# pidbot.net
KiCad netlist of a schematic drawn in Altium Designer
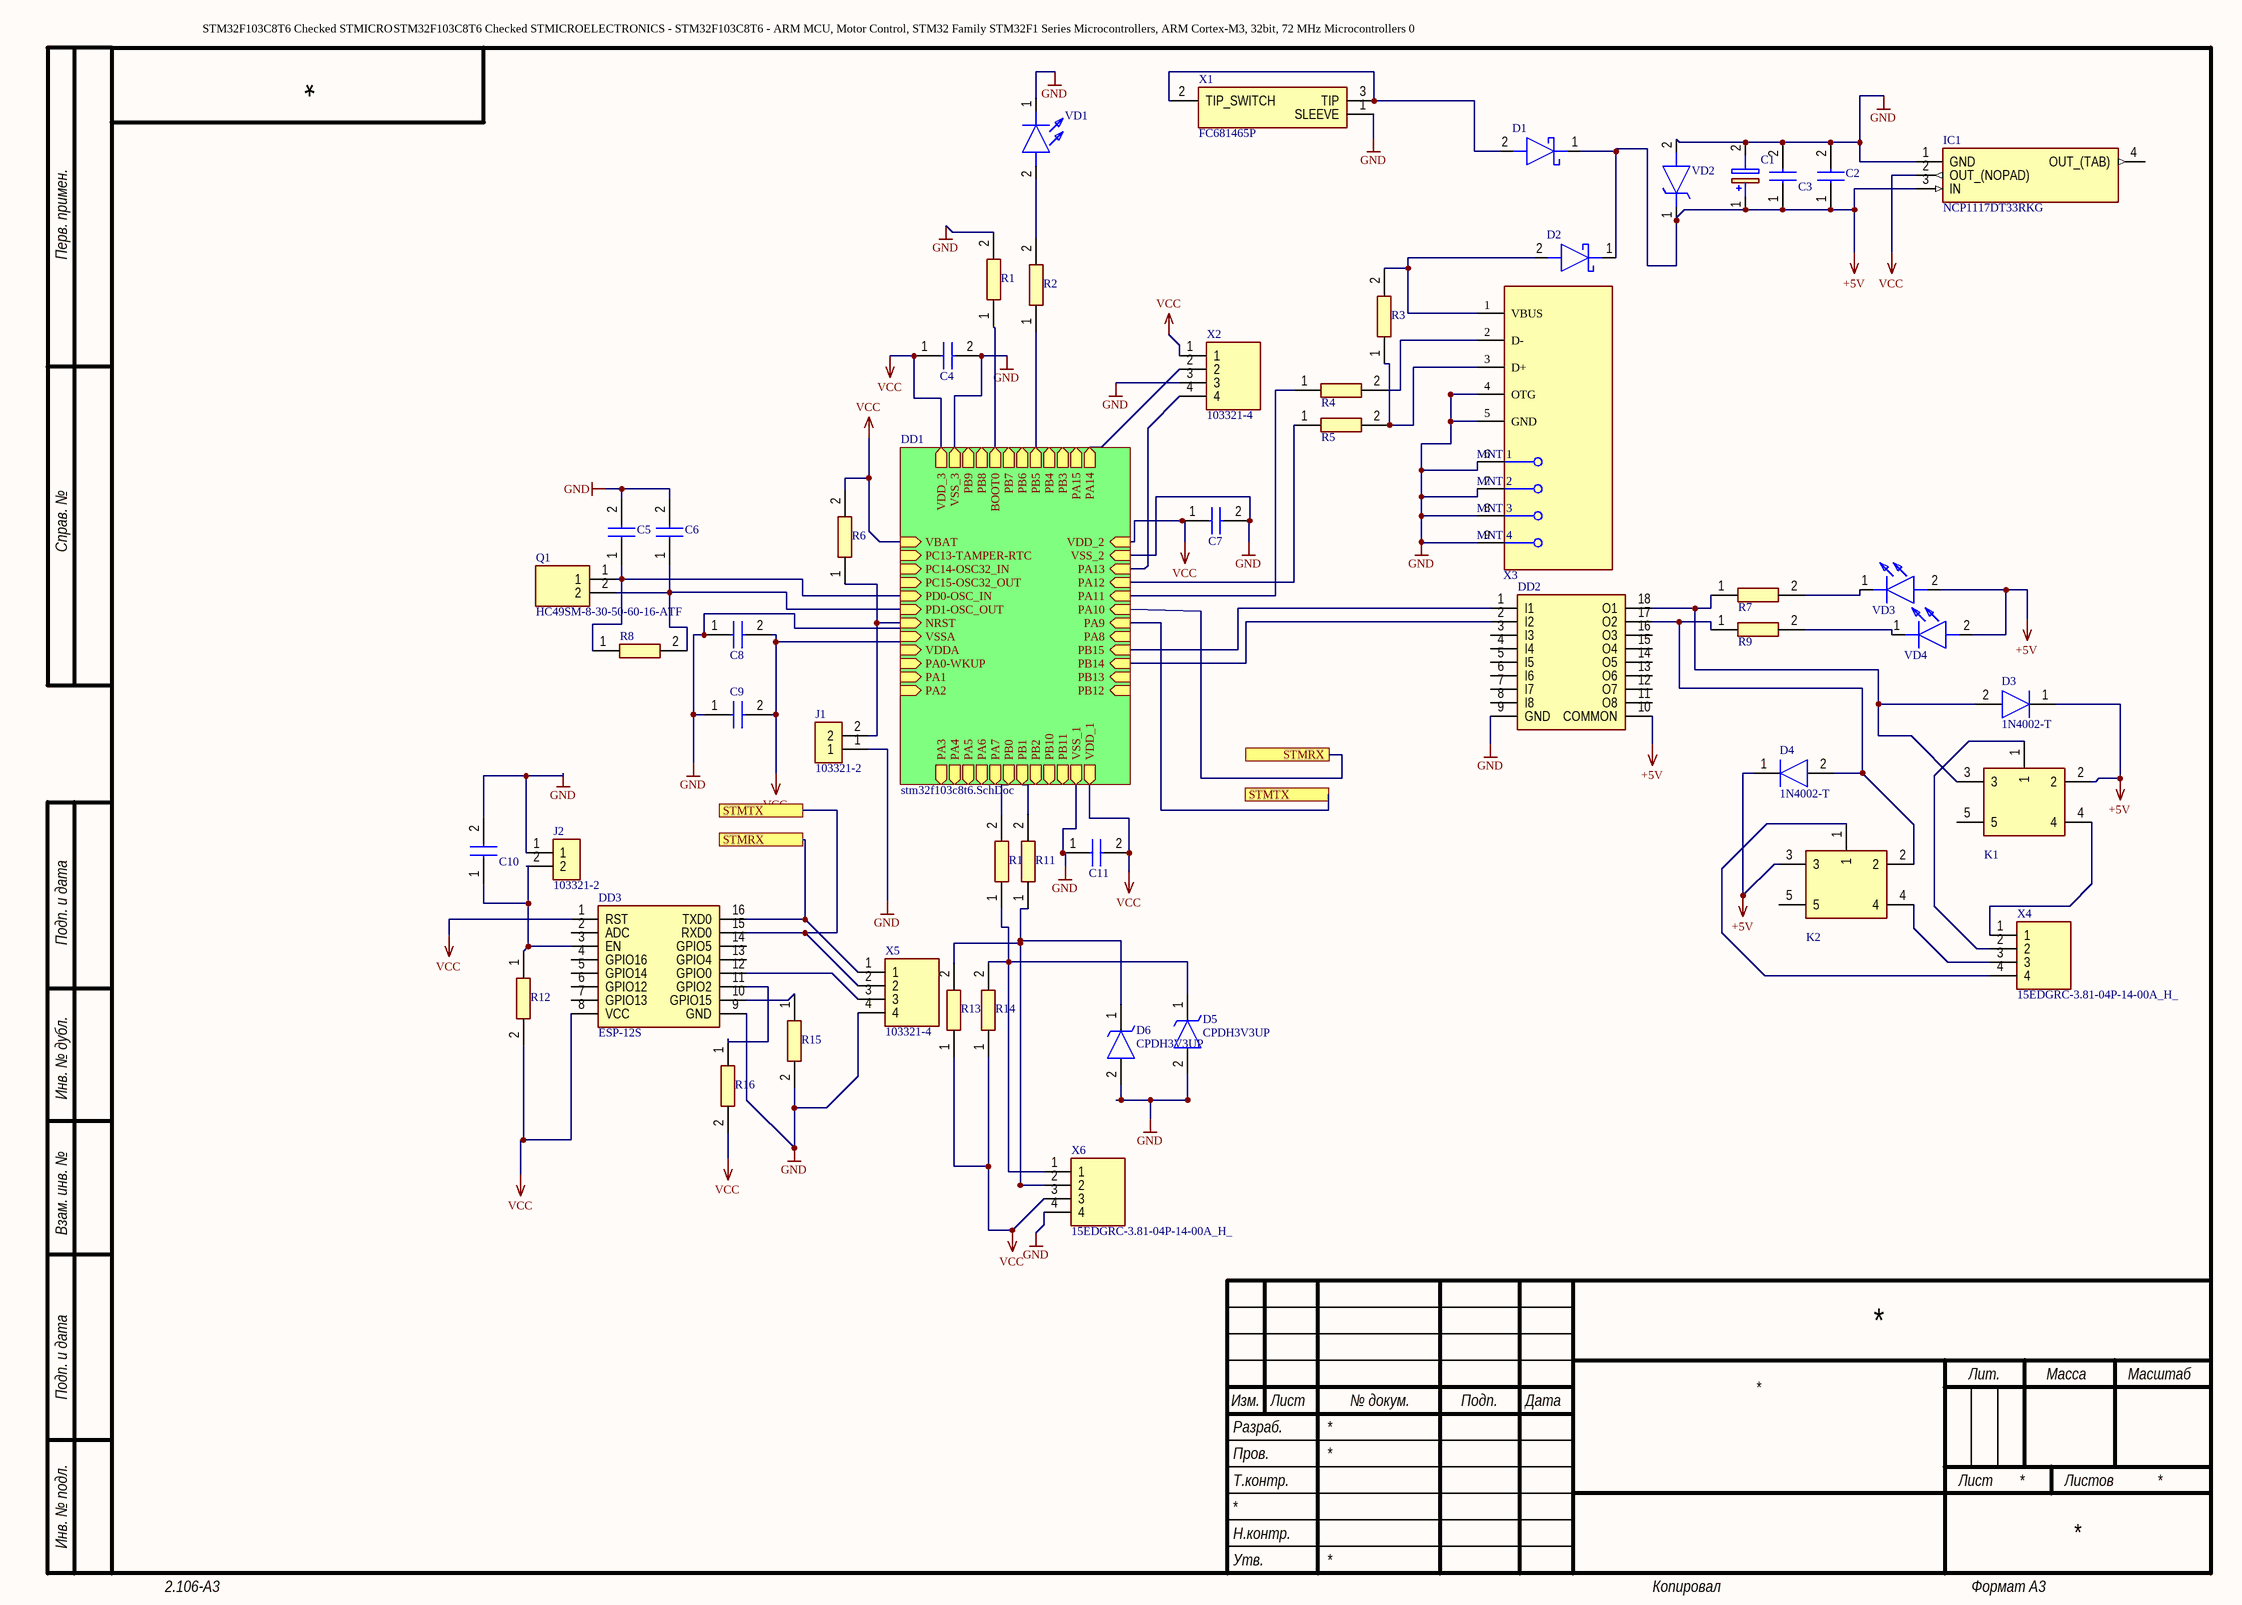
[diagram p0: pidbot.SchDoc]

(export (version "E")
  (design (tool "Eeschema 10.0.6"))
  (components
    (comp (ref "C1")
      (value "470uF(CPOL)")
      (footprint "SamacSys:CAPAE530X610N")
      (description "Capacitor Polarised")
      (fields (field (name "MANUFACTURER_PART_NUMBER") "EEEFK0J470R"))
      (libsource (lib "*") (part "EEEFK0J470R"))
    )
    (comp (ref "C2")
      (value "10uF(0805)")
      (footprint "SamacSys:CAPC2012X145N")
      (description "Capacitor")
      (fields
        (field (name "MANUFACTURER_PART_NUMBER") "C2012X6S1A106K125AB")
        (field (name "MOUSER PART NUMBER") "810-C2012X6S1A106K1B")
      )
      (libsource (lib "*") (part "C2012X6S1A106K125AB"))
    )
    (comp (ref "C3")
      (value "0.1uF(0603)")
      (footprint "SamacSys:CAPC1608X90N")
      (description "Capacitor")
      (fields
        (field (name "MANUFACTURER_PART_NUMBER") "06035A270FAT2A")
        (field (name "MOUSER PART NUMBER") "581-06035A270FAT2A")
      )
      (libsource (lib "*") (part "06035A270FAT2A"))
    )
    (comp (ref "C4")
      (value "0.1uF(0603)")
      (footprint "SamacSys:CAPC1608X90N")
      (description "Capacitor")
      (fields
        (field (name "MANUFACTURER_PART_NUMBER") "06035A270FAT2A")
        (field (name "MOUSER PART NUMBER") "581-06035A270FAT2A")
      )
      (libsource (lib "*") (part "06035A270FAT2A"))
    )
    (comp (ref "C5")
      (value "27pF(0603)")
      (footprint "SamacSys:CAPC1608X90N")
      (description "Capacitor")
      (fields
        (field (name "MANUFACTURER_PART_NUMBER") "06035A270FAT2A")
        (field (name "MOUSER PART NUMBER") "581-06035A270FAT2A")
      )
      (libsource (lib "*") (part "06035A270FAT2A"))
    )
    (comp (ref "C6")
      (value "27pF(0603)")
      (footprint "SamacSys:CAPC1608X90N")
      (description "Capacitor")
      (fields
        (field (name "MANUFACTURER_PART_NUMBER") "06035A270FAT2A")
        (field (name "MOUSER PART NUMBER") "581-06035A270FAT2A")
      )
      (libsource (lib "*") (part "06035A270FAT2A"))
    )
    (comp (ref "C7")
      (value "0.1uF(0603)")
      (footprint "SamacSys:CAPC1608X90N")
      (description "Capacitor")
      (fields
        (field (name "MANUFACTURER_PART_NUMBER") "06035A270FAT2A")
        (field (name "MOUSER PART NUMBER") "581-06035A270FAT2A")
      )
      (libsource (lib "*") (part "06035A270FAT2A"))
    )
    (comp (ref "C8")
      (value "0.1uF(0603)")
      (footprint "SamacSys:CAPC1608X90N")
      (description "Capacitor")
      (fields
        (field (name "MANUFACTURER_PART_NUMBER") "06035A270FAT2A")
        (field (name "MOUSER PART NUMBER") "581-06035A270FAT2A")
      )
      (libsource (lib "*") (part "06035A270FAT2A"))
    )
    (comp (ref "C9")
      (value "10uF(0805)")
      (footprint "SamacSys:CAPC2012X145N")
      (description "Capacitor")
      (fields
        (field (name "MANUFACTURER_PART_NUMBER") "C2012X6S1A106K125AB")
        (field (name "MOUSER PART NUMBER") "810-C2012X6S1A106K1B")
      )
      (libsource (lib "*") (part "C2012X6S1A106K125AB"))
    )
    (comp (ref "C10")
      (value "10uF(0805)")
      (footprint "SamacSys:CAPC2012X145N")
      (description "Capacitor")
      (fields
        (field (name "MANUFACTURER_PART_NUMBER") "C2012X6S1A106K125AB")
        (field (name "MOUSER PART NUMBER") "810-C2012X6S1A106K1B")
      )
      (libsource (lib "*") (part "C2012X6S1A106K125AB"))
    )
    (comp (ref "C11")
      (value "0.1uF(0603)")
      (footprint "SamacSys:CAPC1608X90N")
      (description "Capacitor")
      (fields
        (field (name "MANUFACTURER_PART_NUMBER") "06035A270FAT2A")
        (field (name "MOUSER PART NUMBER") "581-06035A270FAT2A")
      )
      (libsource (lib "*") (part "06035A270FAT2A"))
    )
    (comp (ref "D1")
      (value "SS14FL")
      (footprint "SamacSys:SODFL3617X108N")
      (description "Schottky Diode")
      (fields (field (name "MOUSER PART NUMBER") "512-SS14FL"))
      (libsource (lib "*") (part "SS14FL"))
    )
    (comp (ref "D2")
      (value "SS14FL")
      (footprint "SamacSys:SODFL3617X108N")
      (description "Schottky Diode")
      (fields (field (name "MOUSER PART NUMBER") "512-SS14FL"))
      (libsource (lib "*") (part "SS14FL"))
    )
    (comp (ref "D3")
      (value "1N4002-T")
      (footprint "SamacSys:DIOAD1408W86L464D236")
      (description "Diode")
      (fields (field (name "MOUSER PART NUMBER") "621-1N4002-T"))
      (libsource (lib "*") (part "1N4002-T"))
    )
    (comp (ref "D4")
      (value "1N4002-T")
      (footprint "SamacSys:DIOAD1408W86L464D236")
      (description "Diode")
      (fields (field (name "MOUSER PART NUMBER") "621-1N4002-T"))
      (libsource (lib "*") (part "1N4002-T"))
    )
    (comp (ref "D5")
      (value "CPDH3V3UP")
      (footprint "SamacSys:CPDH3V3UP")
      (description "TVS Diode (Uni-directional)")
      (fields (field (name "MOUSER PART NUMBER") "750-CPDH3V3UP"))
      (libsource (lib "*") (part "CPDH3V3UP"))
    )
    (comp (ref "D6")
      (value "CPDH3V3UP")
      (footprint "SamacSys:CPDH3V3UP")
      (description "TVS Diode (Uni-directional)")
      (fields (field (name "MOUSER PART NUMBER") "750-CPDH3V3UP"))
      (libsource (lib "*") (part "CPDH3V3UP"))
    )
    (comp (ref "DD2")
      (value "ULN2803AFWG,C,EL")
      (footprint "SamacSys:SOIC127P1032X285-18N")
      (description "Integrated Circuit")
      (libsource (lib "*") (part "ULN2803AFWG,C,EL"))
    )
    (comp (ref "DD3")
      (value "ESP-12S")
      (footprint "SamacSys:ESP12S")
      (description "Integrated Circuit")
      (fields (field (name "MOUSER PART NUMBER") "223-ESP-12S"))
      (libsource (lib "*") (part "ESP-12S"))
    )
    (comp (ref "IC1")
      (value "NCP1117DT33RKG")
      (footprint "SamacSys:TO229P990X238-4N")
      (description "Integrated Circuit")
      (fields (field (name "MOUSER PART NUMBER") "863-NCP1117DT33RKG"))
      (libsource (lib "*") (part "NCP1117DT33RKG"))
    )
    (comp (ref "J1")
      (value "103321-2")
      (footprint "SamacSys:HDRV4W66P0X254_1X2_975X234X1036P")
      (description "Connector")
      (fields
        (field (name "MANUFACTURER_PART_NUMBER") "103321-4")
        (field (name "MOUSER PART NUMBER") "571-1033214")
      )
      (libsource (lib "") (part "103321-2_1"))
    )
    (comp (ref "J2")
      (value "103321-2")
      (footprint "SamacSys:HDRV4W66P0X254_1X2_975X234X1036P")
      (description "Connector")
      (fields
        (field (name "MANUFACTURER_PART_NUMBER") "103321-4")
        (field (name "MOUSER PART NUMBER") "571-1033214")
      )
      (libsource (lib "SamacSys") (part "103321-2"))
    )
    (comp (ref "K1")
      (value "SRD-05VDC-SL-C")
      (footprint "SamacSys:SRD")
      (description "Relay or Contactor")
      (libsource (lib "*") (part "SRD-05VDC-SL-C"))
    )
    (comp (ref "K2")
      (value "SRD-05VDC-SL-C")
      (footprint "SamacSys:SRD")
      (description "Relay or Contactor")
      (libsource (lib "*") (part "SRD-05VDC-SL-C"))
    )
    (comp (ref "Q1")
      (value "HC49SM-8-30-50-60-16-ATF")
      (footprint "SamacSys:HC49SM830506016ATF")
      (description "Crystal or Oscillator")
      (libsource (lib "*") (part "HC49SM-8-30-50-60-16-ATF"))
    )
    (comp (ref "R1")
      (value "10K(0603)")
      (footprint "SamacSys:RESC1608X50N")
      (description "Resistor")
      (fields
        (field (name "MANUFACTURER_PART_NUMBER") "CRCW06031M10FKEA")
        (field (name "MOUSER PART NUMBER") "71-CRCW06031M10FKEA")
      )
      (libsource (lib "") (part "CRCW06031M10FKEA_2"))
    )
    (comp (ref "R2")
      (value "330(0603)")
      (footprint "SamacSys:RESC1608X50N")
      (description "Resistor")
      (fields
        (field (name "MANUFACTURER_PART_NUMBER") "CRCW06031M10FKEA")
        (field (name "MOUSER PART NUMBER") "71-CRCW06031M10FKEA")
      )
      (libsource (lib "") (part "CRCW06031M10FKEA_2"))
    )
    (comp (ref "R3")
      (value "1500(0603)")
      (footprint "SamacSys:RESC1608X50N")
      (description "Resistor")
      (fields
        (field (name "MANUFACTURER_PART_NUMBER") "CRCW06031M10FKEA")
        (field (name "MOUSER PART NUMBER") "71-CRCW06031M10FKEA")
      )
      (libsource (lib "") (part "CRCW06031M10FKEA_2"))
    )
    (comp (ref "R4")
      (value "22(0603)")
      (footprint "SamacSys:RESC1608X50N")
      (description "Resistor")
      (fields
        (field (name "MANUFACTURER_PART_NUMBER") "CRCW06031M10FKEA")
        (field (name "MOUSER PART NUMBER") "71-CRCW06031M10FKEA")
      )
      (libsource (lib "*") (part "CRCW06031M10FKEA"))
    )
    (comp (ref "R5")
      (value "22(0603)")
      (footprint "SamacSys:RESC1608X50N")
      (description "Resistor")
      (fields
        (field (name "MANUFACTURER_PART_NUMBER") "CRCW06031M10FKEA")
        (field (name "MOUSER PART NUMBER") "71-CRCW06031M10FKEA")
      )
      (libsource (lib "*") (part "CRCW06031M10FKEA"))
    )
    (comp (ref "R6")
      (value "10K(0603)")
      (footprint "SamacSys:RESC1608X50N")
      (description "Resistor")
      (fields
        (field (name "MANUFACTURER_PART_NUMBER") "CRCW06031M10FKEA")
        (field (name "MOUSER PART NUMBER") "71-CRCW06031M10FKEA")
      )
      (libsource (lib "") (part "CRCW06031M10FKEA_2"))
    )
    (comp (ref "R7")
      (value "470(0603)")
      (footprint "SamacSys:RESC1608X50N")
      (description "Resistor")
      (fields
        (field (name "MANUFACTURER_PART_NUMBER") "CRCW06031M10FKEA")
        (field (name "MOUSER PART NUMBER") "71-CRCW06031M10FKEA")
      )
      (libsource (lib "*") (part "CRCW06031M10FKEA"))
    )
    (comp (ref "R8")
      (value "1M(0603)")
      (footprint "SamacSys:RESC1608X50N")
      (description "Resistor")
      (fields
        (field (name "MANUFACTURER_PART_NUMBER") "CRCW06031M10FKEA")
        (field (name "MOUSER PART NUMBER") "71-CRCW06031M10FKEA")
      )
      (libsource (lib "*") (part "CRCW06031M10FKEA"))
    )
    (comp (ref "R9")
      (value "470(0603)")
      (footprint "SamacSys:RESC1608X50N")
      (description "Resistor")
      (fields
        (field (name "MANUFACTURER_PART_NUMBER") "CRCW06031M10FKEA")
        (field (name "MOUSER PART NUMBER") "71-CRCW06031M10FKEA")
      )
      (libsource (lib "*") (part "CRCW06031M10FKEA"))
    )
    (comp (ref "R10")
      (value "10(0603)")
      (footprint "SamacSys:RESC1608X50N")
      (description "Resistor")
      (fields
        (field (name "MANUFACTURER_PART_NUMBER") "CRCW06031M10FKEA")
        (field (name "MOUSER PART NUMBER") "71-CRCW06031M10FKEA")
      )
      (libsource (lib "") (part "CRCW06031M10FKEA_2"))
    )
    (comp (ref "R11")
      (value "10(0603)")
      (footprint "SamacSys:RESC1608X50N")
      (description "Resistor")
      (fields
        (field (name "MANUFACTURER_PART_NUMBER") "CRCW06031M10FKEA")
        (field (name "MOUSER PART NUMBER") "71-CRCW06031M10FKEA")
      )
      (libsource (lib "") (part "CRCW06031M10FKEA_2"))
    )
    (comp (ref "R12")
      (value "1K(0603)")
      (footprint "SamacSys:RESC1608X50N")
      (description "Resistor")
      (fields
        (field (name "MANUFACTURER_PART_NUMBER") "CRCW06031M10FKEA")
        (field (name "MOUSER PART NUMBER") "71-CRCW06031M10FKEA")
      )
      (libsource (lib "") (part "CRCW06031M10FKEA_1"))
    )
    (comp (ref "R13")
      (value "10K(0603)")
      (footprint "SamacSys:RESC1608X50N")
      (description "Resistor")
      (fields
        (field (name "MANUFACTURER_PART_NUMBER") "CRCW06031M10FKEA")
        (field (name "MOUSER PART NUMBER") "71-CRCW06031M10FKEA")
      )
      (libsource (lib "") (part "CRCW06031M10FKEA_2"))
    )
    (comp (ref "R14")
      (value "10K(0603)")
      (footprint "SamacSys:RESC1608X50N")
      (description "Resistor")
      (fields
        (field (name "MANUFACTURER_PART_NUMBER") "CRCW06031M10FKEA")
        (field (name "MOUSER PART NUMBER") "71-CRCW06031M10FKEA")
      )
      (libsource (lib "") (part "CRCW06031M10FKEA_2"))
    )
    (comp (ref "R15")
      (value "1K(0603)")
      (footprint "SamacSys:RESC1608X50N")
      (description "Resistor")
      (fields
        (field (name "MANUFACTURER_PART_NUMBER") "CRCW06031M10FKEA")
        (field (name "MOUSER PART NUMBER") "71-CRCW06031M10FKEA")
      )
      (libsource (lib "") (part "CRCW06031M10FKEA_1"))
    )
    (comp (ref "R16")
      (value "1K(0603)")
      (footprint "SamacSys:RESC1608X50N")
      (description "Resistor")
      (fields
        (field (name "MANUFACTURER_PART_NUMBER") "CRCW06031M10FKEA")
        (field (name "MOUSER PART NUMBER") "71-CRCW06031M10FKEA")
      )
      (libsource (lib "") (part "CRCW06031M10FKEA_1"))
    )
    (comp (ref "VD1")
      (value "KP-2012SGC")
      (footprint "SamacSys:LEDC2012X110N")
      (description "LED")
      (libsource (lib "*") (part "KP-2012SGC"))
    )
    (comp (ref "VD2")
      (value "1N4733AUR")
      (footprint "SamacSys:DO-213AB")
      (description "Zener Diode")
      (fields (field (name "MOUSER PART NUMBER") "494-1N4733AUR"))
      (libsource (lib "*") (part "1N4733AUR"))
    )
    (comp (ref "VD3")
      (value "KP-2012SGC")
      (footprint "SamacSys:LEDC2012X110N")
      (description "LED")
      (libsource (lib "*") (part "KP-2012SGC"))
    )
    (comp (ref "VD4")
      (value "KP-2012SGC")
      (footprint "SamacSys:LEDC2012X110N")
      (description "LED")
      (libsource (lib "*") (part "KP-2012SGC"))
    )
    (comp (ref "X1")
      (value "FC681465P")
      (footprint "SamacSys:FC681465P")
      (description "Connector")
      (libsource (lib "*") (part "FC681465P"))
    )
    (comp (ref "X2")
      (value "103321-4")
      (footprint "SamacSys:HDRV4W66P0X254_1X4_975X234X1036P")
      (description "Connector")
      (fields (field (name "MOUSER PART NUMBER") "571-1033214"))
      (libsource (lib "*") (part "103321-4"))
    )
    (comp (ref "X3") (value "*") (footprint "pidbot:Wurth_0_MFG") (libsource (lib "*") (part "629105150521")))
    (comp (ref "X4")
      (value "15EDGRC-3.81-04P-14-00A_H_")
      (footprint "SamacSys:SHDRRA4W80P0X381_1X4_1603X920X754P")
      (description "Connector")
      (fields (field (name "MANUFACTURER_PART_NUMBER") "15EDGRC-3.81-04P-14-00A(H)"))
      (libsource (lib "*") (part "15EDGRC-3.81-04P-14-00A_H_"))
    )
    (comp (ref "X5")
      (value "103321-4")
      (footprint "SamacSys:HDRV4W66P0X254_1X4_975X234X1036P")
      (description "Connector")
      (fields (field (name "MOUSER PART NUMBER") "571-1033214"))
      (libsource (lib "*") (part "103321-4"))
    )
    (comp (ref "X6")
      (value "15EDGRC-3.81-04P-14-00A_H_")
      (footprint "SamacSys:SHDRRA4W80P0X381_1X4_1603X920X754P")
      (description "Connector")
      (fields (field (name "MANUFACTURER_PART_NUMBER") "15EDGRC-3.81-04P-14-00A(H)"))
      (libsource (lib "*") (part "15EDGRC-3.81-04P-14-00A_H_"))
    )
  )
  (nets
    (net (code "1") (name "+5V") (class "Default")
      (node (ref "C1") (pin "1") (pinfunction "+_1") (pintype "passive"))
      (node (ref "C2") (pin "1") (pinfunction "1_1") (pintype "passive"))
      (node (ref "C3") (pin "1") (pinfunction "1_1") (pintype "passive"))
      (node (ref "D1") (pin "1") (pinfunction "K_1") (pintype "passive"))
      (node (ref "D2") (pin "1") (pinfunction "K_1") (pintype "passive"))
      (node (ref "D3") (pin "1") (pinfunction "K_1") (pintype "passive"))
      (node (ref "D4") (pin "1") (pinfunction "K_1") (pintype "passive"))
      (node (ref "DD2") (pin "10") (pinfunction "COMMON_10") (pintype "passive"))
      (node (ref "IC1") (pin "3") (pinfunction "IN_3") (pintype "input"))
      (node (ref "K1") (pin "2") (pinfunction "2_2") (pintype "passive"))
      (node (ref "K2") (pin "3") (pinfunction "3_3") (pintype "passive"))
      (node (ref "VD2") (pin "1") (pinfunction "K_1") (pintype "passive"))
      (node (ref "VD3") (pin "2") (pinfunction "A_2") (pintype "passive"))
      (node (ref "VD4") (pin "2") (pinfunction "A_2") (pintype "passive"))
    )
    (net (code "2") (name "/BOOT0") (class "Default")
      (node (ref "R1") (pin "1") (pinfunction "1_1") (pintype "passive"))
    )
    (net (code "3") (name "/NRST") (class "Default")
      (node (ref "J1") (pin "2") (pinfunction "2_2") (pintype "passive"))
      (node (ref "R6") (pin "1") (pinfunction "1_1") (pintype "passive"))
    )
    (net (code "13") (name "/PA11") (class "Default")
      (node (ref "R4") (pin "1") (pinfunction "1_1") (pintype "passive"))
    )
    (net (code "14") (name "/PA12") (class "Default")
      (node (ref "R5") (pin "1") (pinfunction "1_1") (pintype "passive"))
    )
    (net (code "15") (name "/PA13") (class "Default")
      (node (ref "X2") (pin "4") (pinfunction "4_4") (pintype "passive"))
    )
    (net (code "16") (name "/PA14") (class "Default")
      (node (ref "X2") (pin "2") (pinfunction "2_2") (pintype "passive"))
    )
    (net (code "18") (name "/PB0") (class "Default")
      (node (ref "R10") (pin "2") (pinfunction "2_2") (pintype "passive"))
    )
    (net (code "19") (name "/PB1") (class "Default")
      (node (ref "R11") (pin "2") (pinfunction "2_2") (pintype "passive"))
    )
    (net (code "23") (name "/PB5") (class "Default")
      (node (ref "R2") (pin "1") (pinfunction "1_1") (pintype "passive"))
    )
    (net (code "32") (name "/PB14") (class "Default")
      (node (ref "DD2") (pin "2") (pinfunction "I2_2") (pintype "passive"))
    )
    (net (code "33") (name "/PB15") (class "Default")
      (node (ref "DD2") (pin "1") (pinfunction "I1_1") (pintype "passive"))
    )
    (net (code "37") (name "/PD0-OSC_IN") (class "Default")
      (node (ref "C5") (pin "1") (pinfunction "1_1") (pintype "passive"))
      (node (ref "Q1") (pin "1") (pinfunction "1_1") (pintype "passive"))
      (node (ref "R8") (pin "1") (pinfunction "1_1") (pintype "passive"))
    )
    (net (code "38") (name "/PD1-OSC_OUT") (class "Default")
      (node (ref "C6") (pin "1") (pinfunction "1_1") (pintype "passive"))
      (node (ref "Q1") (pin "2") (pinfunction "2_2") (pintype "passive"))
      (node (ref "R8") (pin "2") (pinfunction "2_2") (pintype "passive"))
    )
    (net (code "39") (name "/STMRX") (class "Default")
      (node (ref "DD3") (pin "16") (pinfunction "TXD0_16") (pintype "passive"))
      (node (ref "X5") (pin "1") (pinfunction "1_1") (pintype "passive"))
    )
    (net (code "40") (name "/STMTX") (class "Default")
      (node (ref "DD3") (pin "15") (pinfunction "RXD0_15") (pintype "passive"))
      (node (ref "X5") (pin "2") (pinfunction "2_2") (pintype "passive"))
    )
    (net (code "41") (name "GND") (class "Default")
      (node (ref "C1") (pin "2") (pinfunction "-_2") (pintype "passive"))
      (node (ref "C10") (pin "2") (pinfunction "2_2") (pintype "passive"))
      (node (ref "C11") (pin "1") (pinfunction "1_1") (pintype "passive"))
      (node (ref "C2") (pin "2") (pinfunction "2_2") (pintype "passive"))
      (node (ref "C3") (pin "2") (pinfunction "2_2") (pintype "passive"))
      (node (ref "C4") (pin "2") (pinfunction "2_2") (pintype "passive"))
      (node (ref "C5") (pin "2") (pinfunction "2_2") (pintype "passive"))
      (node (ref "C6") (pin "2") (pinfunction "2_2") (pintype "passive"))
      (node (ref "C7") (pin "2") (pinfunction "2_2") (pintype "passive"))
      (node (ref "C8") (pin "1") (pinfunction "1_1") (pintype "passive"))
      (node (ref "C9") (pin "1") (pinfunction "1_1") (pintype "passive"))
      (node (ref "D5") (pin "2") (pinfunction "A_2") (pintype "passive"))
      (node (ref "D6") (pin "2") (pinfunction "A_2") (pintype "passive"))
      (node (ref "DD2") (pin "9") (pinfunction "GND_9") (pintype "passive"))
      (node (ref "DD3") (pin "9") (pinfunction "GND_9") (pintype "passive"))
      (node (ref "IC1") (pin "1") (pinfunction "GND_1") (pintype "power_in"))
      (node (ref "J1") (pin "1") (pinfunction "1_1") (pintype "passive"))
      (node (ref "J2") (pin "1") (pinfunction "1_1") (pintype "passive"))
      (node (ref "R1") (pin "2") (pinfunction "2_2") (pintype "passive"))
      (node (ref "R15") (pin "2") (pinfunction "2_2") (pintype "passive"))
      (node (ref "VD1") (pin "1") (pinfunction "K_1") (pintype "passive"))
      (node (ref "VD2") (pin "2") (pinfunction "A_2") (pintype "passive"))
      (node (ref "X1") (pin "1") (pinfunction "SLEEVE_1") (pintype "passive"))
      (node (ref "X2") (pin "3") (pinfunction "3_3") (pintype "passive"))
      (node (ref "X3") (pin "4") (pinfunction "OTG_4") (pintype "passive"))
      (node (ref "X3") (pin "5") (pinfunction "GND_5") (pintype "passive"))
      (node (ref "X3") (pin "6") (pinfunction "MNT_1_6") (pintype "passive"))
      (node (ref "X3") (pin "7") (pinfunction "MNT_2_7") (pintype "passive"))
      (node (ref "X3") (pin "8") (pinfunction "MNT_3_8") (pintype "passive"))
      (node (ref "X3") (pin "9") (pinfunction "MNT_4_9") (pintype "passive"))
      (node (ref "X5") (pin "4") (pinfunction "4_4") (pintype "passive"))
      (node (ref "X6") (pin "4") (pinfunction "4_4") (pintype "passive"))
    )
    (net (code "42") (name "Net-(D1-A)") (class "Default")
      (node (ref "D1") (pin "2") (pinfunction "A_2") (pintype "passive"))
      (node (ref "X1") (pin "2") (pinfunction "TIP_SWITCH_2") (pintype "passive"))
      (node (ref "X1") (pin "3") (pinfunction "TIP_3") (pintype "passive"))
    )
    (net (code "43") (name "Net-(D2-A)") (class "Default")
      (node (ref "D2") (pin "2") (pinfunction "A_2") (pintype "passive"))
      (node (ref "R3") (pin "2") (pinfunction "2_2") (pintype "passive"))
      (node (ref "X3") (pin "1") (pinfunction "VBUS_1") (pintype "passive"))
    )
    (net (code "44") (name "Net-(D3-A)") (class "Default")
      (node (ref "D3") (pin "2") (pinfunction "A_2") (pintype "passive"))
      (node (ref "DD2") (pin "18") (pinfunction "O1_18") (pintype "passive"))
      (node (ref "K1") (pin "3") (pinfunction "3_3") (pintype "passive"))
      (node (ref "R7") (pin "1") (pinfunction "1_1") (pintype "passive"))
    )
    (net (code "45") (name "Net-(D4-A)") (class "Default")
      (node (ref "D4") (pin "2") (pinfunction "A_2") (pintype "passive"))
      (node (ref "DD2") (pin "17") (pinfunction "O2_17") (pintype "passive"))
      (node (ref "K2") (pin "2") (pinfunction "2_2") (pintype "passive"))
      (node (ref "R9") (pin "1") (pinfunction "1_1") (pintype "passive"))
    )
    (net (code "46") (name "Net-(D5-K)") (class "Default")
      (node (ref "D5") (pin "1") (pinfunction "K_1") (pintype "passive"))
      (node (ref "R10") (pin "1") (pinfunction "1_1") (pintype "passive"))
      (node (ref "R14") (pin "2") (pinfunction "2_2") (pintype "passive"))
      (node (ref "X6") (pin "1") (pinfunction "1_1") (pintype "passive"))
    )
    (net (code "47") (name "Net-(D6-K)") (class "Default")
      (node (ref "D6") (pin "1") (pinfunction "K_1") (pintype "passive"))
      (node (ref "R11") (pin "1") (pinfunction "1_1") (pintype "passive"))
      (node (ref "R13") (pin "2") (pinfunction "2_2") (pintype "passive"))
      (node (ref "X6") (pin "2") (pinfunction "2_2") (pintype "passive"))
    )
    (net (code "48") (name "Net-(DD3-EN)") (class "Default")
      (node (ref "C10") (pin "1") (pinfunction "1_1") (pintype "passive"))
      (node (ref "DD3") (pin "3") (pinfunction "EN_3") (pintype "passive"))
      (node (ref "J2") (pin "2") (pinfunction "2_2") (pintype "passive"))
      (node (ref "R12") (pin "1") (pinfunction "1_1") (pintype "passive"))
    )
    (net (code "49") (name "Net-(DD3-GPIO0)") (class "Default")
      (node (ref "DD3") (pin "12") (pinfunction "GPIO0_12") (pintype "passive"))
      (node (ref "X5") (pin "3") (pinfunction "3_3") (pintype "passive"))
    )
    (net (code "50") (name "Net-(DD3-GPIO2)") (class "Default")
      (node (ref "DD3") (pin "11") (pinfunction "GPIO2_11") (pintype "passive"))
      (node (ref "R16") (pin "1") (pinfunction "1_1") (pintype "passive"))
    )
    (net (code "51") (name "Net-(DD3-GPIO15)") (class "Default")
      (node (ref "DD3") (pin "10") (pinfunction "GPIO15_10") (pintype "passive"))
      (node (ref "R15") (pin "1") (pinfunction "1_1") (pintype "passive"))
    )
    (net (code "52") (name "Net-(K1-Pad1)") (class "Default")
      (node (ref "K1") (pin "1") (pinfunction "1_1") (pintype "passive"))
      (node (ref "X4") (pin "2") (pinfunction "2_2") (pintype "passive"))
    )
    (net (code "53") (name "Net-(K1-Pad4)") (class "Default")
      (node (ref "K1") (pin "4") (pinfunction "4_4") (pintype "passive"))
      (node (ref "X4") (pin "1") (pinfunction "1_1") (pintype "passive"))
    )
    (net (code "54") (name "Net-(K2-Pad1)") (class "Default")
      (node (ref "K2") (pin "1") (pinfunction "1_1") (pintype "passive"))
      (node (ref "X4") (pin "4") (pinfunction "4_4") (pintype "passive"))
    )
    (net (code "55") (name "Net-(K2-Pad4)") (class "Default")
      (node (ref "K2") (pin "4") (pinfunction "4_4") (pintype "passive"))
      (node (ref "X4") (pin "3") (pinfunction "3_3") (pintype "passive"))
    )
    (net (code "56") (name "Net-(VD1-A)") (class "Default")
      (node (ref "R2") (pin "2") (pinfunction "2_2") (pintype "passive"))
      (node (ref "VD1") (pin "2") (pinfunction "A_2") (pintype "passive"))
    )
    (net (code "57") (name "Net-(VD3-K)") (class "Default")
      (node (ref "R7") (pin "2") (pinfunction "2_2") (pintype "passive"))
      (node (ref "VD3") (pin "1") (pinfunction "K_1") (pintype "passive"))
    )
    (net (code "58") (name "Net-(VD4-K)") (class "Default")
      (node (ref "R9") (pin "2") (pinfunction "2_2") (pintype "passive"))
      (node (ref "VD4") (pin "1") (pinfunction "K_1") (pintype "passive"))
    )
    (net (code "59") (name "Net-(X3-D+)") (class "Default")
      (node (ref "R3") (pin "1") (pinfunction "1_1") (pintype "passive"))
      (node (ref "R5") (pin "2") (pinfunction "2_2") (pintype "passive"))
      (node (ref "X3") (pin "3") (pinfunction "D+_3") (pintype "passive"))
    )
    (net (code "60") (name "Net-(X3-D-)") (class "Default")
      (node (ref "R4") (pin "2") (pinfunction "2_2") (pintype "passive"))
      (node (ref "X3") (pin "2") (pinfunction "D-_2") (pintype "passive"))
    )
    (net (code "61") (name "VCC") (class "Default")
      (node (ref "C11") (pin "2") (pinfunction "2_2") (pintype "passive"))
      (node (ref "C4") (pin "1") (pinfunction "1_1") (pintype "passive"))
      (node (ref "C7") (pin "1") (pinfunction "1_1") (pintype "passive"))
      (node (ref "C8") (pin "2") (pinfunction "2_2") (pintype "passive"))
      (node (ref "C9") (pin "2") (pinfunction "2_2") (pintype "passive"))
      (node (ref "DD3") (pin "1") (pinfunction "RST_1") (pintype "passive"))
      (node (ref "DD3") (pin "8") (pinfunction "VCC_8") (pintype "passive"))
      (node (ref "IC1") (pin "2") (pinfunction "OUT_(NOPAD)_2") (pintype "output"))
      (node (ref "R12") (pin "2") (pinfunction "2_2") (pintype "passive"))
      (node (ref "R13") (pin "1") (pinfunction "1_1") (pintype "passive"))
      (node (ref "R14") (pin "1") (pinfunction "1_1") (pintype "passive"))
      (node (ref "R16") (pin "2") (pinfunction "2_2") (pintype "passive"))
      (node (ref "R6") (pin "2") (pinfunction "2_2") (pintype "passive"))
      (node (ref "X2") (pin "1") (pinfunction "1_1") (pintype "passive"))
      (node (ref "X6") (pin "3") (pinfunction "3_3") (pintype "passive"))
    )
    (net (code "62") (name "unconnected-(DD2-I3-Pad3)") (class "Default")
      (node (ref "DD2") (pin "3") (pinfunction "I3_3") (pintype "passive"))
    )
    (net (code "63") (name "unconnected-(DD2-I4-Pad4)") (class "Default")
      (node (ref "DD2") (pin "4") (pinfunction "I4_4") (pintype "passive"))
    )
    (net (code "64") (name "unconnected-(DD2-I5-Pad5)") (class "Default")
      (node (ref "DD2") (pin "5") (pinfunction "I5_5") (pintype "passive"))
    )
    (net (code "65") (name "unconnected-(DD2-I6-Pad6)") (class "Default")
      (node (ref "DD2") (pin "6") (pinfunction "I6_6") (pintype "passive"))
    )
    (net (code "66") (name "unconnected-(DD2-I7-Pad7)") (class "Default")
      (node (ref "DD2") (pin "7") (pinfunction "I7_7") (pintype "passive"))
    )
    (net (code "67") (name "unconnected-(DD2-I8-Pad8)") (class "Default")
      (node (ref "DD2") (pin "8") (pinfunction "I8_8") (pintype "passive"))
    )
    (net (code "68") (name "unconnected-(DD2-O3-Pad16)") (class "Default")
      (node (ref "DD2") (pin "16") (pinfunction "O3_16") (pintype "passive"))
    )
    (net (code "69") (name "unconnected-(DD2-O4-Pad15)") (class "Default")
      (node (ref "DD2") (pin "15") (pinfunction "O4_15") (pintype "passive"))
    )
    (net (code "70") (name "unconnected-(DD2-O5-Pad14)") (class "Default")
      (node (ref "DD2") (pin "14") (pinfunction "O5_14") (pintype "passive"))
    )
    (net (code "71") (name "unconnected-(DD2-O6-Pad13)") (class "Default")
      (node (ref "DD2") (pin "13") (pinfunction "O6_13") (pintype "passive"))
    )
    (net (code "72") (name "unconnected-(DD2-O7-Pad12)") (class "Default")
      (node (ref "DD2") (pin "12") (pinfunction "O7_12") (pintype "passive"))
    )
    (net (code "73") (name "unconnected-(DD2-O8-Pad11)") (class "Default")
      (node (ref "DD2") (pin "11") (pinfunction "O8_11") (pintype "passive"))
    )
    (net (code "74") (name "unconnected-(DD3-ADC-Pad2)") (class "Default")
      (node (ref "DD3") (pin "2") (pinfunction "ADC_2") (pintype "passive"))
    )
    (net (code "75") (name "unconnected-(DD3-GPIO4-Pad13)") (class "Default")
      (node (ref "DD3") (pin "13") (pinfunction "GPIO4_13") (pintype "passive"))
    )
    (net (code "76") (name "unconnected-(DD3-GPIO5-Pad14)") (class "Default")
      (node (ref "DD3") (pin "14") (pinfunction "GPIO5_14") (pintype "passive"))
    )
    (net (code "77") (name "unconnected-(DD3-GPIO12-Pad6)") (class "Default")
      (node (ref "DD3") (pin "6") (pinfunction "GPIO12_6") (pintype "passive"))
    )
    (net (code "78") (name "unconnected-(DD3-GPIO13-Pad7)") (class "Default")
      (node (ref "DD3") (pin "7") (pinfunction "GPIO13_7") (pintype "passive"))
    )
    (net (code "79") (name "unconnected-(DD3-GPIO14-Pad5)") (class "Default")
      (node (ref "DD3") (pin "5") (pinfunction "GPIO14_5") (pintype "passive"))
    )
    (net (code "80") (name "unconnected-(DD3-GPIO16-Pad4)") (class "Default")
      (node (ref "DD3") (pin "4") (pinfunction "GPIO16_4") (pintype "passive"))
    )
    (net (code "81") (name "unconnected-(IC1-OUT_(TAB)-Pad4)") (class "Default")
      (node (ref "IC1") (pin "4") (pinfunction "OUT_(TAB)_4") (pintype "output"))
    )
    (net (code "82") (name "unconnected-(K1-Pad5)") (class "Default")
      (node (ref "K1") (pin "5") (pinfunction "5_5") (pintype "passive"))
    )
    (net (code "83") (name "unconnected-(K2-Pad5)") (class "Default")
      (node (ref "K2") (pin "5") (pinfunction "5_5") (pintype "passive"))
    )
  )
)
